# homegreen_node_basic_v1_4_4.net
KiCad netlist of a schematic drawn in EAGLE
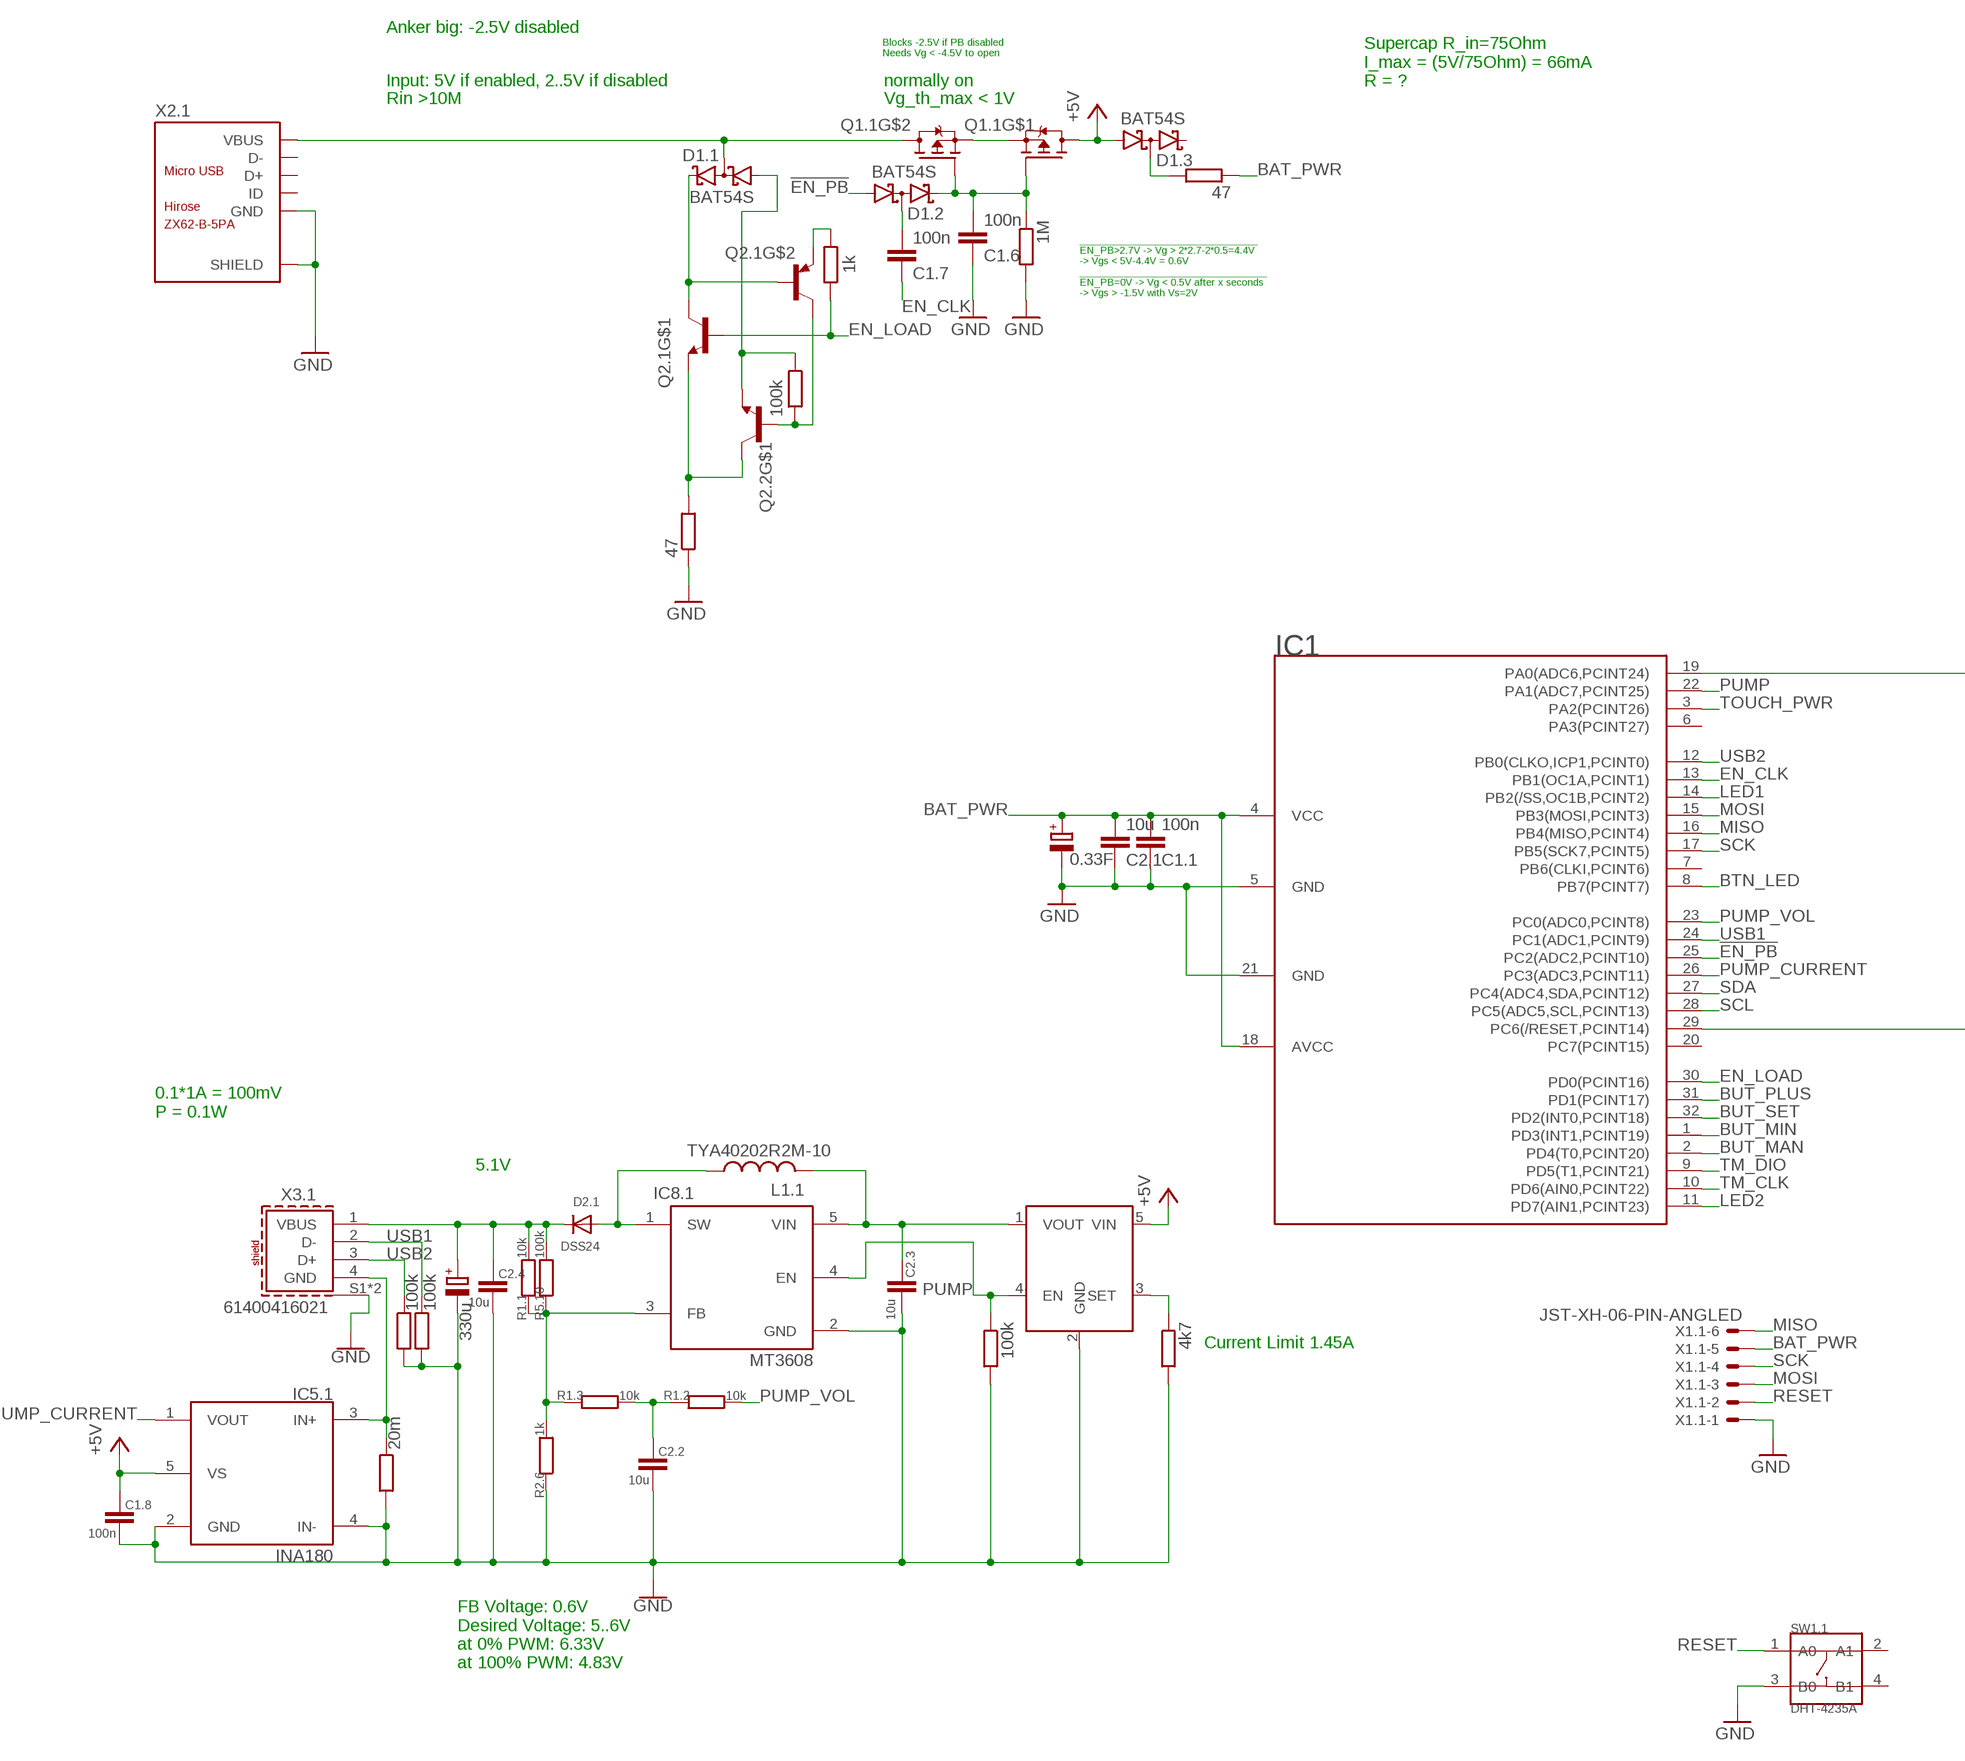
[diagram p0: schematic, sheet 1, part 1 of 2]
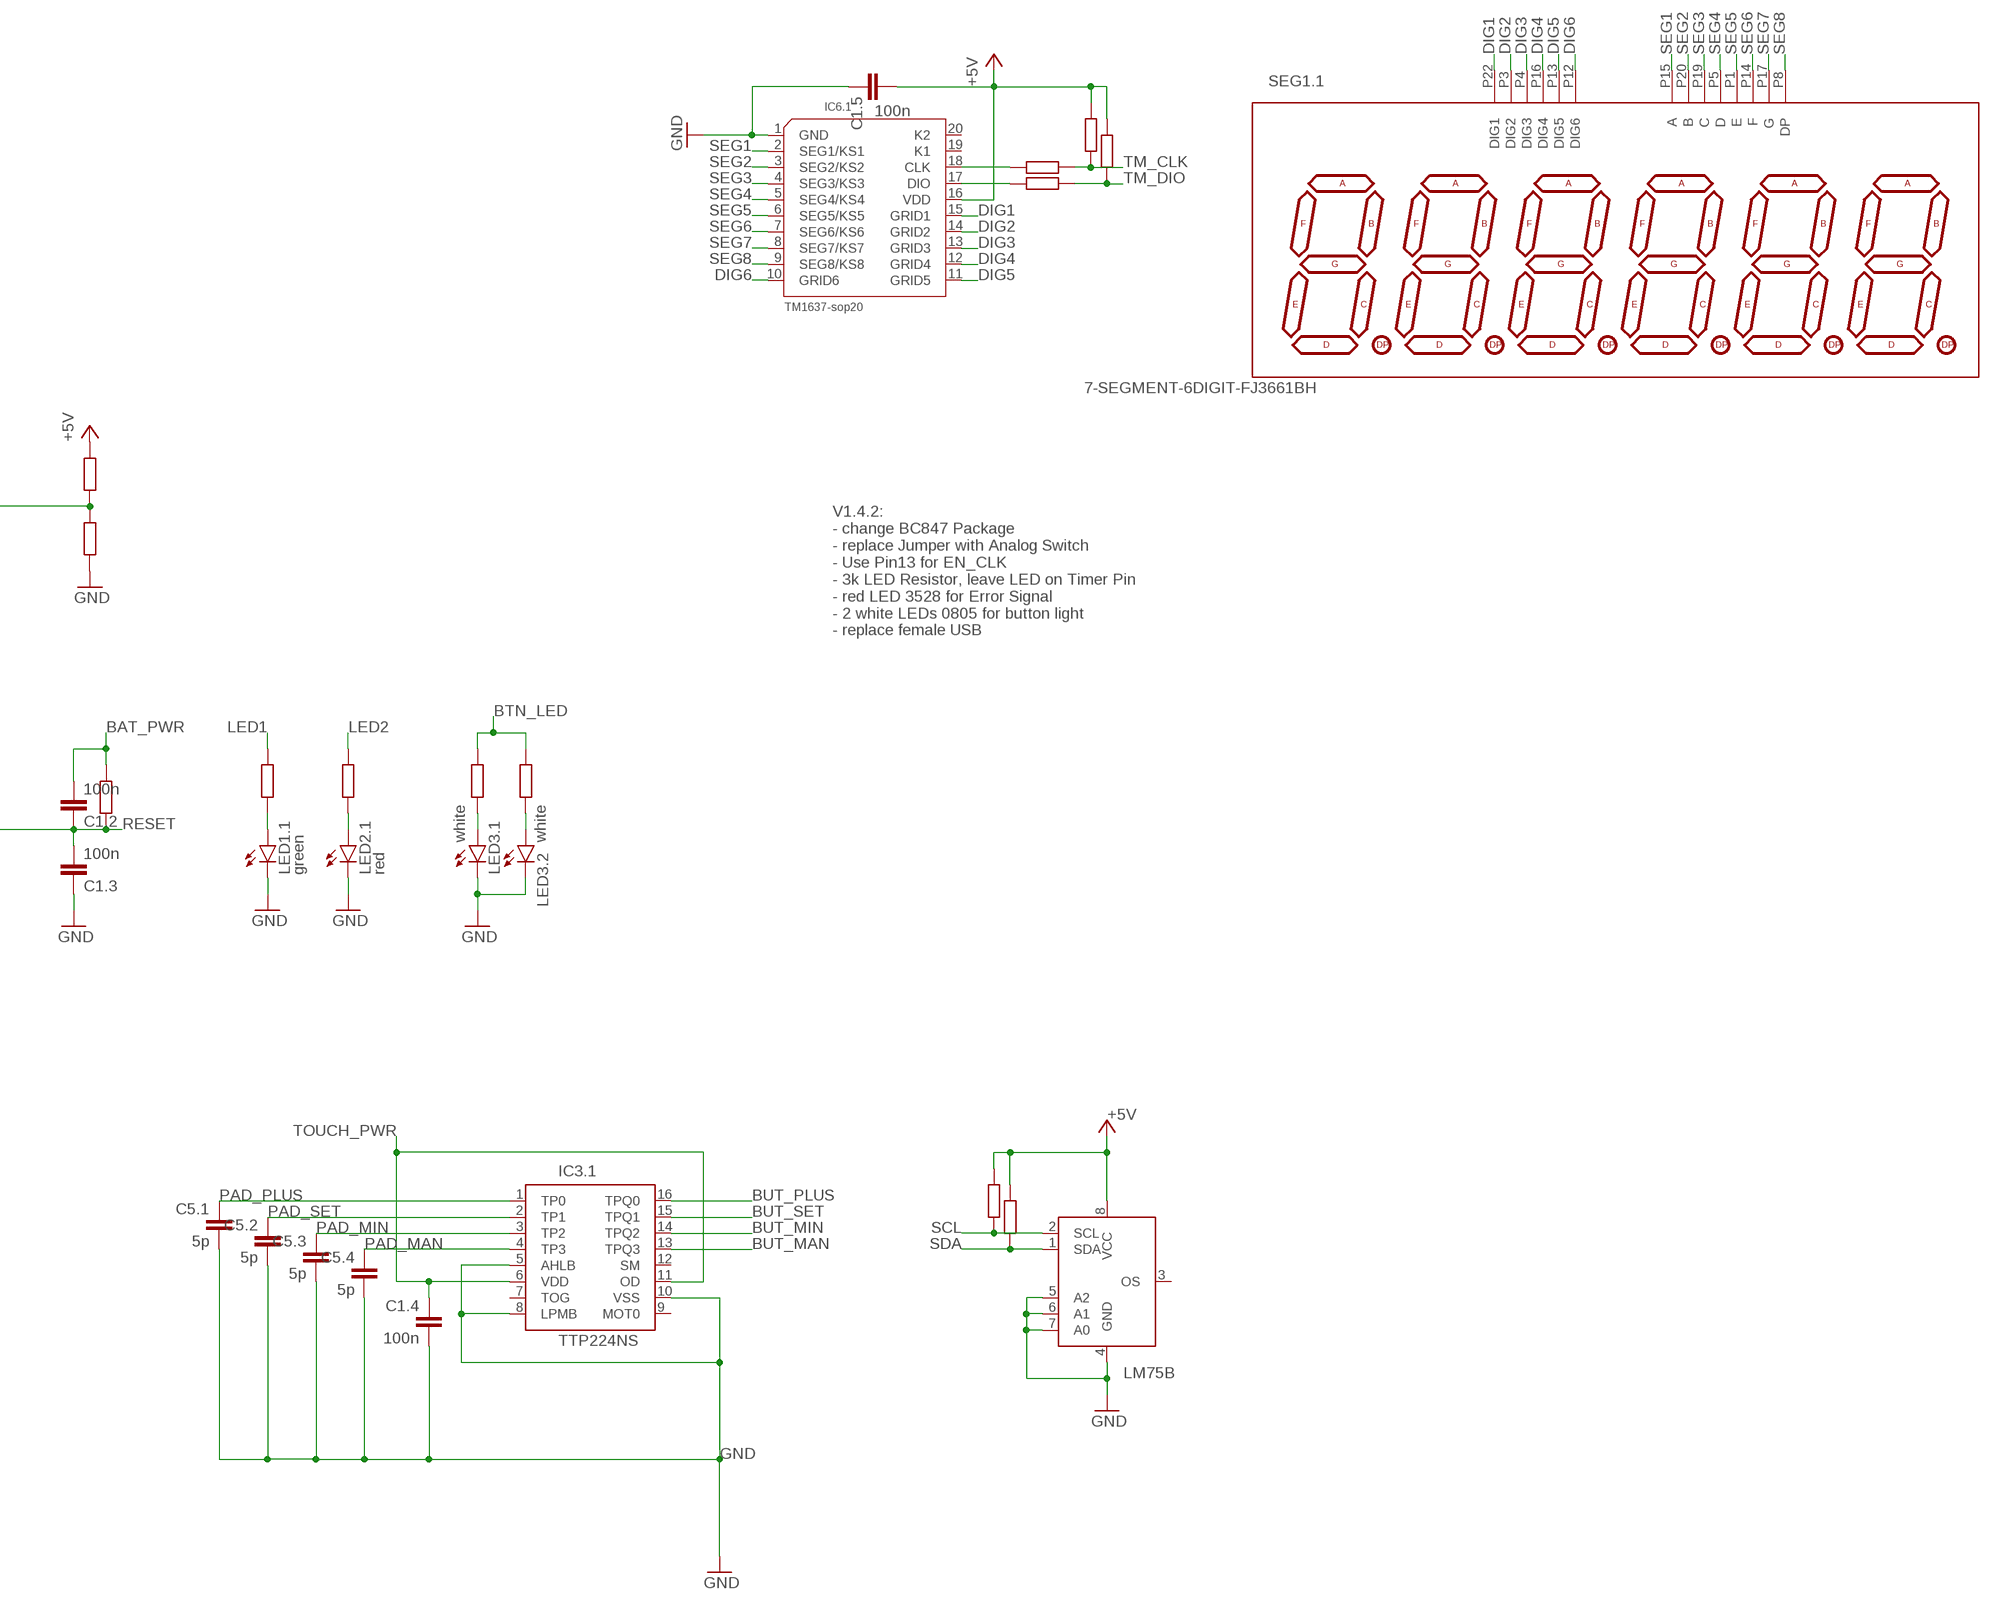
[diagram p1: schematic, sheet 1, part 2 of 2]

(export (version "E")
  (design (tool "Eeschema 10.0.6"))
  (components
    (comp (ref "C1.1")
      (value "100n")
      (footprint "eagle-import:C0805")
      (libsource (lib "eagle-import") (part "C-EUC0805"))
    )
    (comp (ref "C1.2")
      (value "100n")
      (footprint "eagle-import:C0805")
      (libsource (lib "eagle-import") (part "C-EUC0805"))
    )
    (comp (ref "C1.3")
      (value "100n")
      (footprint "eagle-import:C0805")
      (libsource (lib "eagle-import") (part "C-EUC0805"))
    )
    (comp (ref "C1.4")
      (value "100n")
      (footprint "eagle-import:C0805")
      (libsource (lib "eagle-import") (part "C-EUC0805"))
    )
    (comp (ref "C1.5")
      (value "100n")
      (footprint "eagle-import:C0805")
      (libsource (lib "eagle-import") (part "C-EUC0805"))
    )
    (comp (ref "C1.6")
      (value "100n")
      (footprint "eagle-import:C0805")
      (libsource (lib "eagle-import") (part "C-EUC0805"))
    )
    (comp (ref "C1.7")
      (value "100n")
      (footprint "eagle-import:C0805")
      (libsource (lib "eagle-import") (part "C-EUC0805"))
    )
    (comp (ref "C1.8")
      (value "100n")
      (footprint "eagle-import:C0805")
      (libsource (lib "eagle-import") (part "resistor_348_C-EUC0805"))
    )
    (comp (ref "C2.1")
      (value "10u")
      (footprint "eagle-import:C0805")
      (libsource (lib "eagle-import") (part "C-EUC0805"))
    )
    (comp (ref "C2.2")
      (value "10u")
      (footprint "eagle-import:C0805")
      (libsource (lib "eagle-import") (part "resistor_348_C-EUC0805"))
    )
    (comp (ref "C2.3")
      (value "10u")
      (footprint "eagle-import:C0805")
      (libsource (lib "eagle-import") (part "resistor_348_C-EUC0805"))
    )
    (comp (ref "C2.4")
      (value "10u")
      (footprint "eagle-import:C0805")
      (libsource (lib "eagle-import") (part "resistor_348_C-EUC0805"))
    )
    (comp (ref "C3.1")
      (value "0.33F")
      (footprint "eagle-import:C_FYD0H104ZF")
      (libsource (lib "eagle-import") (part "SUPERCAP"))
    )
    (comp (ref "C4.1")
      (value "330u")
      (footprint "eagle-import:PANASONIC_D")
      (libsource (lib "eagle-import") (part "CPOL-EUD"))
    )
    (comp (ref "C5.1")
      (value "5p")
      (footprint "eagle-import:C0805")
      (libsource (lib "eagle-import") (part "C-EUC0805"))
    )
    (comp (ref "C5.2")
      (value "5p")
      (footprint "eagle-import:C0805")
      (libsource (lib "eagle-import") (part "C-EUC0805"))
    )
    (comp (ref "C5.3")
      (value "5p")
      (footprint "eagle-import:C0805")
      (libsource (lib "eagle-import") (part "C-EUC0805"))
    )
    (comp (ref "C5.4")
      (value "5p")
      (footprint "eagle-import:C0805")
      (libsource (lib "eagle-import") (part "C-EUC0805"))
    )
    (comp (ref "D1.1")
      (value "BAT54S")
      (footprint "eagle-import:SOT23")
      (libsource (lib "eagle-import") (part "BAT54S"))
    )
    (comp (ref "D1.2")
      (value "BAT54S")
      (footprint "eagle-import:SOT23")
      (libsource (lib "eagle-import") (part "BAT54S"))
    )
    (comp (ref "D1.3")
      (value "BAT54S")
      (footprint "eagle-import:SOT23")
      (libsource (lib "eagle-import") (part "BAT54S"))
    )
    (comp (ref "D2.1")
      (value "DSS24")
      (footprint "eagle-import:SOD-123")
      (libsource (lib "eagle-import") (part "DIODE_SOD123"))
    )
    (comp (ref "IC1")
      (value "ATTINY88")
      (footprint "eagle-import:TQFP32-08")
      (libsource (lib "eagle-import") (part "ATTINY88"))
    )
    (comp (ref "IC2.1")
      (value "LM75B")
      (footprint "eagle-import:SO8")
      (libsource (lib "eagle-import") (part "LM75B"))
    )
    (comp (ref "IC3.1")
      (value "TTP224NS")
      (footprint "eagle-import:SSOP16")
      (libsource (lib "eagle-import") (part "TTP224NS"))
    )
    (comp (ref "IC4.1")
      (value "MT9700MT9700")
      (footprint "eagle-import:SOT23-5")
      (libsource (lib "eagle-import") (part "MT9700MT9700"))
    )
    (comp (ref "IC5.1")
      (value "INA180")
      (footprint "eagle-import:SOT23-5")
      (libsource (lib "eagle-import") (part "INA180"))
    )
    (comp (ref "IC6.1")
      (value "TM1637-sop20")
      (footprint "eagle-import:SOP20-1.27-12.7X7.65MM")
      (fields (field (name "MPN") "TM1637"))
      (libsource (lib "eagle-import") (part "DRIVER-TM1637(SOP20)"))
    )
    (comp (ref "IC8.1")
      (value "MT3608")
      (footprint "eagle-import:SOT23-6")
      (libsource (lib "eagle-import") (part "MT3608"))
    )
    (comp (ref "L1.1")
      (value "TYA40202R2M-10")
      (footprint "eagle-import:WE-LQSH_4020")
      (libsource (lib "eagle-import") (part "WE-LQSH_4020_744050420047"))
    )
    (comp (ref "LED1.1")
      (value "green")
      (footprint "eagle-import:KA-3528ASYC")
      (libsource (lib "eagle-import") (part "LEDKA-3528ASYC"))
    )
    (comp (ref "LED2.1")
      (value "red")
      (footprint "eagle-import:KA-3528ASYC")
      (libsource (lib "eagle-import") (part "LEDKA-3528ASYC"))
    )
    (comp (ref "LED3.1")
      (value "white")
      (footprint "eagle-import:CHIPLED_0805")
      (libsource (lib "eagle-import") (part "LEDCHIPLED_0805"))
    )
    (comp (ref "LED3.2")
      (value "white")
      (footprint "eagle-import:CHIPLED_0805")
      (libsource (lib "eagle-import") (part "LEDCHIPLED_0805"))
    )
    (comp (ref "Q1.1")
      (value "WST2011")
      (footprint "eagle-import:SOT23-6")
      (libsource (lib "eagle-import") (part "CJL2623SOT23-6"))
    )
    (comp (ref "Q2.1")
      (value "BC817DPN")
      (footprint "eagle-import:SOT23-6")
      (libsource (lib "eagle-import") (part "BC817DPN"))
    )
    (comp (ref "Q2.2")
      (value "BC817DPN")
      (footprint "eagle-import:SOT23-6")
      (libsource (lib "eagle-import") (part "BC817DPN"))
    )
    (comp (ref "R1.1")
      (value "10k")
      (footprint "eagle-import:R0805")
      (libsource (lib "eagle-import") (part "resistor_348_R-EU_R0805"))
    )
    (comp (ref "R1.2")
      (value "10k")
      (footprint "eagle-import:R0805")
      (libsource (lib "eagle-import") (part "resistor_348_R-EU_R0805"))
    )
    (comp (ref "R1.3")
      (value "10k")
      (footprint "eagle-import:R0805")
      (libsource (lib "eagle-import") (part "resistor_348_R-EU_R0805"))
    )
    (comp (ref "R2.1")
      (value "1k")
      (footprint "eagle-import:R0805")
      (libsource (lib "eagle-import") (part "R-EU_R0805"))
    )
    (comp (ref "R2.2")
      (value "1k")
      (footprint "eagle-import:R0805")
      (libsource (lib "eagle-import") (part "R-EU_R0805"))
    )
    (comp (ref "R2.3")
      (value "1k")
      (footprint "eagle-import:R0805")
      (libsource (lib "eagle-import") (part "R-EU_R0805"))
    )
    (comp (ref "R2.4")
      (value "1k")
      (footprint "eagle-import:R0805")
      (libsource (lib "eagle-import") (part "R-EU_R0805"))
    )
    (comp (ref "R2.5")
      (value "1k")
      (footprint "eagle-import:R0805")
      (libsource (lib "eagle-import") (part "R-EU_R0805"))
    )
    (comp (ref "R2.6")
      (value "1k")
      (footprint "eagle-import:R0805")
      (libsource (lib "eagle-import") (part "resistor_348_R-EU_R0805"))
    )
    (comp (ref "R3.1")
      (value "47")
      (footprint "eagle-import:R0805")
      (libsource (lib "eagle-import") (part "R-EU_R0805"))
    )
    (comp (ref "R3.2")
      (value "47")
      (footprint "eagle-import:R0805")
      (libsource (lib "eagle-import") (part "R-EU_R0805"))
    )
    (comp (ref "R4.1")
      (value "3k")
      (footprint "eagle-import:R0805")
      (libsource (lib "eagle-import") (part "R-EU_R0805"))
    )
    (comp (ref "R4.2")
      (value "3k")
      (footprint "eagle-import:R0805")
      (libsource (lib "eagle-import") (part "R-EU_R0805"))
    )
    (comp (ref "R5.1")
      (value "100k")
      (footprint "eagle-import:R0805")
      (libsource (lib "eagle-import") (part "R-EU_R0805"))
    )
    (comp (ref "R5.2")
      (value "100k")
      (footprint "eagle-import:R0805")
      (libsource (lib "eagle-import") (part "R-EU_R0805"))
    )
    (comp (ref "R5.3")
      (value "100k")
      (footprint "eagle-import:R0805")
      (libsource (lib "eagle-import") (part "R-EU_R0805"))
    )
    (comp (ref "R5.4")
      (value "100k")
      (footprint "eagle-import:R0805")
      (libsource (lib "eagle-import") (part "R-EU_R0805"))
    )
    (comp (ref "R5.5")
      (value "100k")
      (footprint "eagle-import:R0805")
      (libsource (lib "eagle-import") (part "R-EU_R0805"))
    )
    (comp (ref "R5.6")
      (value "100k")
      (footprint "eagle-import:R0805")
      (libsource (lib "eagle-import") (part "R-EU_R0805"))
    )
    (comp (ref "R5.7")
      (value "100k")
      (footprint "eagle-import:R0805")
      (libsource (lib "eagle-import") (part "R-EU_R0805"))
    )
    (comp (ref "R5.8")
      (value "100k")
      (footprint "eagle-import:R0805")
      (libsource (lib "eagle-import") (part "R-EU_R0805"))
    )
    (comp (ref "R5.9")
      (value "100k")
      (footprint "eagle-import:R0805")
      (libsource (lib "eagle-import") (part "R-EU_R0805"))
    )
    (comp (ref "R5.10")
      (value "100k")
      (footprint "eagle-import:R0805")
      (libsource (lib "eagle-import") (part "resistor_348_R-EU_R0805"))
    )
    (comp (ref "R6.1")
      (value "1M")
      (footprint "eagle-import:R0805")
      (libsource (lib "eagle-import") (part "R-EU_R0805"))
    )
    (comp (ref "R7.1")
      (value "4k7")
      (footprint "eagle-import:R0805")
      (libsource (lib "eagle-import") (part "R-EU_R0805"))
    )
    (comp (ref "R7.2")
      (value "4k7")
      (footprint "eagle-import:R0805")
      (libsource (lib "eagle-import") (part "R-EU_R0805"))
    )
    (comp (ref "R7.3")
      (value "4k7")
      (footprint "eagle-import:R0805")
      (libsource (lib "eagle-import") (part "R-EU_R0805"))
    )
    (comp (ref "R8.1")
      (value "20m")
      (footprint "eagle-import:R0805")
      (libsource (lib "eagle-import") (part "R-EU_R0805"))
    )
    (comp (ref "SEG1.1")
      (value "7-SEGMENT-6DIGIT-FJ3661BH")
      (footprint "eagle-import:7SEG_6D_FJ3661BH")
      (libsource (lib "eagle-import") (part "7-SEGMENT-6DIGIT-FJ3661BH"))
    )
    (comp (ref "SW1.1")
      (value "DHT-4235A")
      (footprint "eagle-import:SW4-SMD-4.2X3.2X2.5MM")
      (libsource (lib "eagle-import") (part "SMD-BUTTON-TOP-DHT-4235A(4P-4.2X3.2MM)"))
    )
    (comp (ref "X1.1")
      (value "JST-XH-06-PIN-ANGLED")
      (footprint "eagle-import:JST-XH-06-PACKAGE-ROUND-PAD-ANGLED")
      (libsource (lib "eagle-import") (part "JST-XH-06-PIN-ANGLED"))
    )
    (comp (ref "X2.1")
      (value "ZX62-B-5PA")
      (footprint "eagle-import:ZX62-B-5PA")
      (libsource (lib "eagle-import") (part "MICRO-USB-SMD(ZX62-B-5PA)"))
    )
    (comp (ref "X3.1")
      (value "61400416021")
      (footprint "eagle-import:61400416021")
      (libsource (lib "eagle-import") (part "61400416021"))
    )
  )
  (nets
    (net (code "1") (name "+5V") (class "Default")
      (node (ref "C1.5") (pin "2") (pinfunction "2_2") (pintype "passive"))
      (node (ref "C1.8") (pin "1") (pinfunction "1_1") (pintype "passive"))
      (node (ref "D1.3") (pin "1") (pinfunction "A1_1") (pintype "passive"))
      (node (ref "IC2.1") (pin "8") (pinfunction "VCC_8") (pintype "power_in"))
      (node (ref "IC4.1") (pin "5") (pinfunction "VIN_5") (pintype "bidirectional"))
      (node (ref "IC5.1") (pin "5") (pinfunction "VS_5") (pintype "bidirectional"))
      (node (ref "IC6.1") (pin "16") (pinfunction "VDD_16") (pintype "bidirectional"))
      (node (ref "Q1.1") (pin "6") (pinfunction "D_6") (pintype "passive"))
      (node (ref "R5.3") (pin "1") (pinfunction "1_1") (pintype "passive"))
      (node (ref "R5.5") (pin "2") (pinfunction "2_2") (pintype "passive"))
      (node (ref "R5.6") (pin "2") (pinfunction "2_2") (pintype "passive"))
      (node (ref "R7.2") (pin "2") (pinfunction "2_2") (pintype "passive"))
      (node (ref "R7.3") (pin "2") (pinfunction "2_2") (pintype "passive"))
    )
    (net (code "2") (name "/BAT_PWR") (class "Default")
      (node (ref "C1.1") (pin "2") (pinfunction "2_2") (pintype "passive"))
      (node (ref "C1.2") (pin "2") (pinfunction "2_2") (pintype "passive"))
      (node (ref "C2.1") (pin "2") (pinfunction "2_2") (pintype "passive"))
      (node (ref "C3.1") (pin "+") (pinfunction "+_+") (pintype "passive"))
      (node (ref "IC1") (pin "18") (pinfunction "AVCC_18") (pintype "power_in"))
      (node (ref "IC1") (pin "4") (pinfunction "VCC_4") (pintype "power_in"))
      (node (ref "R3.2") (pin "1") (pinfunction "1_1") (pintype "passive"))
      (node (ref "R5.7") (pin "1") (pinfunction "1_1") (pintype "passive"))
      (node (ref "X1.1") (pin "5") (pinfunction "S_5") (pintype "passive"))
    )
    (net (code "3") (name "/BTN_LED") (class "Default")
      (node (ref "IC1") (pin "8") (pinfunction "PB7(PCINT7)_8") (pintype "bidirectional"))
      (node (ref "R2.1") (pin "2") (pinfunction "2_2") (pintype "passive"))
      (node (ref "R2.5") (pin "2") (pinfunction "2_2") (pintype "passive"))
    )
    (net (code "4") (name "/BUT_MAN") (class "Default")
      (node (ref "IC1") (pin "2") (pinfunction "PD4(T0,PCINT20)_2") (pintype "bidirectional"))
      (node (ref "IC3.1") (pin "13") (pinfunction "TPQ3_13") (pintype "bidirectional"))
    )
    (net (code "5") (name "/BUT_MIN") (class "Default")
      (node (ref "IC1") (pin "1") (pinfunction "PD3(INT1,PCINT19)_1") (pintype "bidirectional"))
      (node (ref "IC3.1") (pin "14") (pinfunction "TPQ2_14") (pintype "bidirectional"))
    )
    (net (code "6") (name "/BUT_PLUS") (class "Default")
      (node (ref "IC1") (pin "31") (pinfunction "PD1(PCINT17)_31") (pintype "bidirectional"))
      (node (ref "IC3.1") (pin "16") (pinfunction "TPQ0_16") (pintype "bidirectional"))
    )
    (net (code "7") (name "/BUT_SET") (class "Default")
      (node (ref "IC1") (pin "32") (pinfunction "PD2(INT0,PCINT18)_32") (pintype "bidirectional"))
      (node (ref "IC3.1") (pin "15") (pinfunction "TPQ1_15") (pintype "bidirectional"))
    )
    (net (code "8") (name "/DIG1") (class "Default")
      (node (ref "IC6.1") (pin "15") (pinfunction "GRID1_15") (pintype "bidirectional"))
      (node (ref "SEG1.1") (pin "P22") (pinfunction "DIG1_P22") (pintype "bidirectional"))
    )
    (net (code "9") (name "/DIG2") (class "Default")
      (node (ref "IC6.1") (pin "14") (pinfunction "GRID2_14") (pintype "bidirectional"))
      (node (ref "SEG1.1") (pin "P3") (pinfunction "DIG2_P3") (pintype "bidirectional"))
    )
    (net (code "10") (name "/DIG3") (class "Default")
      (node (ref "IC6.1") (pin "13") (pinfunction "GRID3_13") (pintype "bidirectional"))
      (node (ref "SEG1.1") (pin "P4") (pinfunction "DIG3_P4") (pintype "bidirectional"))
    )
    (net (code "11") (name "/DIG4") (class "Default")
      (node (ref "IC6.1") (pin "12") (pinfunction "GRID4_12") (pintype "bidirectional"))
      (node (ref "SEG1.1") (pin "P16") (pinfunction "DIG4_P16") (pintype "bidirectional"))
    )
    (net (code "12") (name "/DIG5") (class "Default")
      (node (ref "IC6.1") (pin "11") (pinfunction "GRID5_11") (pintype "bidirectional"))
      (node (ref "SEG1.1") (pin "P13") (pinfunction "DIG5_P13") (pintype "bidirectional"))
    )
    (net (code "13") (name "/DIG6") (class "Default")
      (node (ref "IC6.1") (pin "10") (pinfunction "GRID6_10") (pintype "bidirectional"))
      (node (ref "SEG1.1") (pin "P12") (pinfunction "DIG6_P12") (pintype "bidirectional"))
    )
    (net (code "14") (name "/EN_CLK") (class "Default")
      (node (ref "C1.7") (pin "1") (pinfunction "1_1") (pintype "passive"))
      (node (ref "IC1") (pin "13") (pinfunction "PB1(OC1A,PCINT1)_13") (pintype "bidirectional"))
    )
    (net (code "15") (name "/EN_LOAD") (class "Default")
      (node (ref "IC1") (pin "30") (pinfunction "PD0(PCINT16)_30") (pintype "bidirectional"))
      (node (ref "Q2.1") (pin "2") (pinfunction "B_2") (pintype "passive"))
      (node (ref "R2.4") (pin "1") (pinfunction "1_1") (pintype "passive"))
    )
    (net (code "16") (name "/LED1") (class "Default")
      (node (ref "IC1") (pin "14") (pinfunction "PB2(/SS,OC1B,PCINT2)_14") (pintype "bidirectional"))
      (node (ref "R4.1") (pin "2") (pinfunction "2_2") (pintype "passive"))
    )
    (net (code "17") (name "/LED2") (class "Default")
      (node (ref "IC1") (pin "11") (pinfunction "PD7(AIN1,PCINT23)_11") (pintype "bidirectional"))
      (node (ref "R4.2") (pin "2") (pinfunction "2_2") (pintype "passive"))
    )
    (net (code "18") (name "/MISO") (class "Default")
      (node (ref "IC1") (pin "16") (pinfunction "PB4(MISO,PCINT4)_16") (pintype "bidirectional"))
      (node (ref "X1.1") (pin "6") (pinfunction "S_6") (pintype "passive"))
    )
    (net (code "19") (name "/MOSI") (class "Default")
      (node (ref "IC1") (pin "15") (pinfunction "PB3(MOSI,PCINT3)_15") (pintype "bidirectional"))
      (node (ref "X1.1") (pin "3") (pinfunction "S_3") (pintype "passive"))
    )
    (net (code "20") (name "/PAD_MAN") (class "Default")
      (node (ref "C5.4") (pin "1") (pinfunction "1_1") (pintype "passive"))
      (node (ref "IC3.1") (pin "4") (pinfunction "TP3_4") (pintype "bidirectional"))
    )
    (net (code "21") (name "/PAD_MIN") (class "Default")
      (node (ref "C5.3") (pin "1") (pinfunction "1_1") (pintype "passive"))
      (node (ref "IC3.1") (pin "3") (pinfunction "TP2_3") (pintype "bidirectional"))
    )
    (net (code "22") (name "/PAD_PLUS") (class "Default")
      (node (ref "C5.1") (pin "1") (pinfunction "1_1") (pintype "passive"))
      (node (ref "IC3.1") (pin "1") (pinfunction "TP0_1") (pintype "bidirectional"))
    )
    (net (code "23") (name "/PAD_SET") (class "Default")
      (node (ref "C5.2") (pin "1") (pinfunction "1_1") (pintype "passive"))
      (node (ref "IC3.1") (pin "2") (pinfunction "TP1_2") (pintype "bidirectional"))
    )
    (net (code "24") (name "/PUMP") (class "Default")
      (node (ref "IC1") (pin "22") (pinfunction "PA1(ADC7,PCINT25)_22") (pintype "bidirectional"))
      (node (ref "IC4.1") (pin "4") (pinfunction "EN_4") (pintype "bidirectional"))
      (node (ref "IC8.1") (pin "4") (pinfunction "EN_4") (pintype "bidirectional"))
      (node (ref "R5.2") (pin "1") (pinfunction "1_1") (pintype "passive"))
    )
    (net (code "25") (name "/PUMP_CURRENT") (class "Default")
      (node (ref "IC1") (pin "26") (pinfunction "PC3(ADC3,PCINT11)_26") (pintype "bidirectional"))
      (node (ref "IC5.1") (pin "1") (pinfunction "VOUT_1") (pintype "bidirectional"))
    )
    (net (code "26") (name "/PUMP_VOL") (class "Default")
      (node (ref "IC1") (pin "23") (pinfunction "PC0(ADC0,PCINT8)_23") (pintype "bidirectional"))
      (node (ref "R1.2") (pin "2") (pinfunction "2_2") (pintype "passive"))
    )
    (net (code "27") (name "/RESET") (class "Default")
      (node (ref "C1.2") (pin "1") (pinfunction "1_1") (pintype "passive"))
      (node (ref "C1.3") (pin "2") (pinfunction "2_2") (pintype "passive"))
      (node (ref "IC1") (pin "29") (pinfunction "PC6(/RESET,PCINT14)_29") (pintype "bidirectional"))
      (node (ref "R5.7") (pin "2") (pinfunction "2_2") (pintype "passive"))
      (node (ref "SW1.1") (pin "1") (pinfunction "A0_1") (pintype "bidirectional"))
      (node (ref "X1.1") (pin "2") (pinfunction "S_2") (pintype "passive"))
    )
    (net (code "28") (name "/SCK") (class "Default")
      (node (ref "IC1") (pin "17") (pinfunction "PB5(SCK7,PCINT5)_17") (pintype "bidirectional"))
      (node (ref "X1.1") (pin "4") (pinfunction "S_4") (pintype "passive"))
    )
    (net (code "29") (name "/SCL") (class "Default")
      (node (ref "IC1") (pin "28") (pinfunction "PC5(ADC5,SCL,PCINT13)_28") (pintype "bidirectional"))
      (node (ref "IC2.1") (pin "2") (pinfunction "SCL_2") (pintype "bidirectional"))
      (node (ref "R7.3") (pin "1") (pinfunction "1_1") (pintype "passive"))
    )
    (net (code "30") (name "/SDA") (class "Default")
      (node (ref "IC1") (pin "27") (pinfunction "PC4(ADC4,SDA,PCINT12)_27") (pintype "bidirectional"))
      (node (ref "IC2.1") (pin "1") (pinfunction "SDA_1") (pintype "bidirectional"))
      (node (ref "R7.2") (pin "1") (pinfunction "1_1") (pintype "passive"))
    )
    (net (code "31") (name "/SEG1") (class "Default")
      (node (ref "IC6.1") (pin "2") (pinfunction "SEG1/KS1_2") (pintype "bidirectional"))
      (node (ref "SEG1.1") (pin "P15") (pinfunction "A_P15") (pintype "bidirectional"))
    )
    (net (code "32") (name "/SEG2") (class "Default")
      (node (ref "IC6.1") (pin "3") (pinfunction "SEG2/KS2_3") (pintype "bidirectional"))
      (node (ref "SEG1.1") (pin "P20") (pinfunction "B_P20") (pintype "bidirectional"))
    )
    (net (code "33") (name "/SEG3") (class "Default")
      (node (ref "IC6.1") (pin "4") (pinfunction "SEG3/KS3_4") (pintype "bidirectional"))
      (node (ref "SEG1.1") (pin "P19") (pinfunction "C_P19") (pintype "bidirectional"))
    )
    (net (code "34") (name "/SEG4") (class "Default")
      (node (ref "IC6.1") (pin "5") (pinfunction "SEG4/KS4_5") (pintype "bidirectional"))
      (node (ref "SEG1.1") (pin "P5") (pinfunction "D_P5") (pintype "bidirectional"))
    )
    (net (code "35") (name "/SEG5") (class "Default")
      (node (ref "IC6.1") (pin "6") (pinfunction "SEG5/KS5_6") (pintype "bidirectional"))
      (node (ref "SEG1.1") (pin "P1") (pinfunction "E_P1") (pintype "bidirectional"))
    )
    (net (code "36") (name "/SEG6") (class "Default")
      (node (ref "IC6.1") (pin "7") (pinfunction "SEG6/KS6_7") (pintype "bidirectional"))
      (node (ref "SEG1.1") (pin "P14") (pinfunction "F_P14") (pintype "bidirectional"))
    )
    (net (code "37") (name "/SEG7") (class "Default")
      (node (ref "IC6.1") (pin "8") (pinfunction "SEG7/KS7_8") (pintype "bidirectional"))
      (node (ref "SEG1.1") (pin "P17") (pinfunction "G_P17") (pintype "bidirectional"))
    )
    (net (code "38") (name "/SEG8") (class "Default")
      (node (ref "IC6.1") (pin "9") (pinfunction "SEG8/KS8_9") (pintype "bidirectional"))
      (node (ref "SEG1.1") (pin "P8") (pinfunction "DP_P8") (pintype "bidirectional"))
    )
    (net (code "39") (name "/TM_CLK") (class "Default")
      (node (ref "IC1") (pin "10") (pinfunction "PD6(AIN0,PCINT22)_10") (pintype "bidirectional"))
      (node (ref "R2.2") (pin "1") (pinfunction "1_1") (pintype "passive"))
      (node (ref "R5.5") (pin "1") (pinfunction "1_1") (pintype "passive"))
    )
    (net (code "40") (name "/TM_DIO") (class "Default")
      (node (ref "IC1") (pin "9") (pinfunction "PD5(T1,PCINT21)_9") (pintype "bidirectional"))
      (node (ref "R2.3") (pin "1") (pinfunction "1_1") (pintype "passive"))
      (node (ref "R5.6") (pin "1") (pinfunction "1_1") (pintype "passive"))
    )
    (net (code "41") (name "/TOUCH_PWR") (class "Default")
      (node (ref "C1.4") (pin "1") (pinfunction "1_1") (pintype "passive"))
      (node (ref "IC1") (pin "3") (pinfunction "PA2(PCINT26)_3") (pintype "bidirectional"))
      (node (ref "IC3.1") (pin "11") (pinfunction "OD_11") (pintype "bidirectional"))
      (node (ref "IC3.1") (pin "6") (pinfunction "VDD_6") (pintype "power_in"))
    )
    (net (code "42") (name "/USB1") (class "Default")
      (node (ref "IC1") (pin "24") (pinfunction "PC1(ADC1,PCINT9)_24") (pintype "bidirectional"))
      (node (ref "R5.9") (pin "1") (pinfunction "1_1") (pintype "passive"))
      (node (ref "X3.1") (pin "2") (pinfunction "D-_2") (pintype "bidirectional"))
    )
    (net (code "43") (name "/USB2") (class "Default")
      (node (ref "IC1") (pin "12") (pinfunction "PB0(CLKO,ICP1,PCINT0)_12") (pintype "bidirectional"))
      (node (ref "R5.8") (pin "1") (pinfunction "1_1") (pintype "passive"))
      (node (ref "X3.1") (pin "3") (pinfunction "D+_3") (pintype "bidirectional"))
    )
    (net (code "44") (name "/~{EN_PB}") (class "Default")
      (node (ref "D1.2") (pin "1") (pinfunction "A1_1") (pintype "passive"))
      (node (ref "IC1") (pin "25") (pinfunction "PC2(ADC2,PCINT10)_25") (pintype "bidirectional"))
    )
    (net (code "45") (name "GND") (class "Default")
      (node (ref "C1.1") (pin "1") (pinfunction "1_1") (pintype "passive"))
      (node (ref "C1.3") (pin "1") (pinfunction "1_1") (pintype "passive"))
      (node (ref "C1.4") (pin "2") (pinfunction "2_2") (pintype "passive"))
      (node (ref "C1.5") (pin "1") (pinfunction "1_1") (pintype "passive"))
      (node (ref "C1.6") (pin "1") (pinfunction "1_1") (pintype "passive"))
      (node (ref "C1.8") (pin "2") (pinfunction "2_2") (pintype "passive"))
      (node (ref "C2.1") (pin "1") (pinfunction "1_1") (pintype "passive"))
      (node (ref "C2.2") (pin "2") (pinfunction "2_2") (pintype "passive"))
      (node (ref "C2.3") (pin "2") (pinfunction "2_2") (pintype "passive"))
      (node (ref "C2.4") (pin "2") (pinfunction "2_2") (pintype "passive"))
      (node (ref "C3.1") (pin "-") (pinfunction "-_-") (pintype "passive"))
      (node (ref "C4.1") (pin "-") (pinfunction "-_-") (pintype "passive"))
      (node (ref "C5.1") (pin "2") (pinfunction "2_2") (pintype "passive"))
      (node (ref "C5.2") (pin "2") (pinfunction "2_2") (pintype "passive"))
      (node (ref "C5.3") (pin "2") (pinfunction "2_2") (pintype "passive"))
      (node (ref "C5.4") (pin "2") (pinfunction "2_2") (pintype "passive"))
      (node (ref "IC1") (pin "21") (pinfunction "GND_21") (pintype "power_in"))
      (node (ref "IC1") (pin "5") (pinfunction "GND_5") (pintype "power_in"))
      (node (ref "IC2.1") (pin "4") (pinfunction "GND_4") (pintype "bidirectional"))
      (node (ref "IC2.1") (pin "5") (pinfunction "A2_5") (pintype "input"))
      (node (ref "IC2.1") (pin "6") (pinfunction "A1_6") (pintype "input"))
      (node (ref "IC2.1") (pin "7") (pinfunction "A0_7") (pintype "input"))
      (node (ref "IC3.1") (pin "10") (pinfunction "VSS_10") (pintype "power_in"))
      (node (ref "IC3.1") (pin "5") (pinfunction "AHLB_5") (pintype "bidirectional"))
      (node (ref "IC3.1") (pin "8") (pinfunction "LPMB_8") (pintype "bidirectional"))
      (node (ref "IC4.1") (pin "2") (pinfunction "GND_2") (pintype "bidirectional"))
      (node (ref "IC5.1") (pin "2") (pinfunction "GND_2") (pintype "bidirectional"))
      (node (ref "IC5.1") (pin "4") (pinfunction "IN-_4") (pintype "bidirectional"))
      (node (ref "IC6.1") (pin "1") (pinfunction "GND_1") (pintype "bidirectional"))
      (node (ref "IC8.1") (pin "2") (pinfunction "GND_2") (pintype "bidirectional"))
      (node (ref "LED1.1") (pin "C") (pinfunction "C_C") (pintype "passive"))
      (node (ref "LED2.1") (pin "C") (pinfunction "C_C") (pintype "passive"))
      (node (ref "LED3.1") (pin "C") (pinfunction "C_C") (pintype "passive"))
      (node (ref "LED3.2") (pin "C") (pinfunction "C_C") (pintype "passive"))
      (node (ref "R2.6") (pin "1") (pinfunction "1_1") (pintype "passive"))
      (node (ref "R3.1") (pin "1") (pinfunction "1_1") (pintype "passive"))
      (node (ref "R5.2") (pin "2") (pinfunction "2_2") (pintype "passive"))
      (node (ref "R5.4") (pin "2") (pinfunction "2_2") (pintype "passive"))
      (node (ref "R5.8") (pin "2") (pinfunction "2_2") (pintype "passive"))
      (node (ref "R5.9") (pin "2") (pinfunction "2_2") (pintype "passive"))
      (node (ref "R6.1") (pin "2") (pinfunction "2_2") (pintype "passive"))
      (node (ref "R7.1") (pin "2") (pinfunction "2_2") (pintype "passive"))
      (node (ref "R8.1") (pin "2") (pinfunction "2_2") (pintype "passive"))
      (node (ref "SW1.1") (pin "3") (pinfunction "B0_3") (pintype "bidirectional"))
      (node (ref "X1.1") (pin "1") (pinfunction "S_1") (pintype "passive"))
      (node (ref "X2.1") (pin "5") (pinfunction "GND_5") (pintype "power_in"))
      (node (ref "X2.1") (pin "P1") (pinfunction "SHIELD_P1") (pintype "power_in"))
      (node (ref "X2.1") (pin "P2") (pinfunction "SHIELD_P2") (pintype "power_in"))
      (node (ref "X2.1") (pin "P3") (pinfunction "SHIELD_P3") (pintype "power_in"))
      (node (ref "X2.1") (pin "P4") (pinfunction "SHIELD_P4") (pintype "power_in"))
      (node (ref "X2.1") (pin "P5") (pinfunction "SHIELD_P5") (pintype "power_in"))
      (node (ref "X2.1") (pin "P6") (pinfunction "SHIELD_P6") (pintype "power_in"))
      (node (ref "X3.1") (pin "S1") (pinfunction "SHIELD_S1") (pintype "bidirectional"))
      (node (ref "X3.1") (pin "S2") (pinfunction "SHIELD_S2") (pintype "bidirectional"))
    )
    (net (code "46") (name "Net-(C2.2-Pad1)") (class "Default")
      (node (ref "C2.2") (pin "1") (pinfunction "1_1") (pintype "passive"))
      (node (ref "R1.2") (pin "1") (pinfunction "1_1") (pintype "passive"))
      (node (ref "R1.3") (pin "2") (pinfunction "2_2") (pintype "passive"))
    )
    (net (code "47") (name "Net-(D1.1-A1)") (class "Default")
      (node (ref "D1.1") (pin "1") (pinfunction "A1_1") (pintype "passive"))
      (node (ref "Q2.2") (pin "1") (pinfunction "E_1") (pintype "passive"))
      (node (ref "R5.1") (pin "1") (pinfunction "1_1") (pintype "passive"))
    )
    (net (code "48") (name "Net-(D1.1-C1A2)") (class "Default")
      (node (ref "D1.1") (pin "3") (pinfunction "C1A2_3") (pintype "passive"))
      (node (ref "Q1.1") (pin "4") (pinfunction "D_4") (pintype "passive"))
      (node (ref "X2.1") (pin "1") (pinfunction "VBUS_1") (pintype "power_in"))
    )
    (net (code "49") (name "Net-(D1.1-C2)") (class "Default")
      (node (ref "D1.1") (pin "2") (pinfunction "C2_2") (pintype "passive"))
      (node (ref "Q2.1") (pin "5") (pinfunction "B_5") (pintype "passive"))
      (node (ref "Q2.1") (pin "6") (pinfunction "C_6") (pintype "passive"))
    )
    (net (code "50") (name "Net-(D1.2-C1A2)") (class "Default")
      (node (ref "C1.7") (pin "2") (pinfunction "2_2") (pintype "passive"))
      (node (ref "D1.2") (pin "3") (pinfunction "C1A2_3") (pintype "passive"))
    )
    (net (code "51") (name "Net-(D1.2-C2)") (class "Default")
      (node (ref "C1.6") (pin "2") (pinfunction "2_2") (pintype "passive"))
      (node (ref "D1.2") (pin "2") (pinfunction "C2_2") (pintype "passive"))
      (node (ref "Q1.1") (pin "1") (pinfunction "G_1") (pintype "passive"))
      (node (ref "Q1.1") (pin "3") (pinfunction "G_3") (pintype "passive"))
      (node (ref "R6.1") (pin "1") (pinfunction "1_1") (pintype "passive"))
    )
    (net (code "52") (name "Net-(D1.3-C1A2)") (class "Default")
      (node (ref "D1.3") (pin "3") (pinfunction "C1A2_3") (pintype "passive"))
      (node (ref "R3.2") (pin "2") (pinfunction "2_2") (pintype "passive"))
    )
    (net (code "53") (name "Net-(IC1-PA0(ADC6,PCINT24))") (class "Default")
      (node (ref "IC1") (pin "19") (pinfunction "PA0(ADC6,PCINT24)_19") (pintype "bidirectional"))
      (node (ref "R5.3") (pin "2") (pinfunction "2_2") (pintype "passive"))
      (node (ref "R5.4") (pin "1") (pinfunction "1_1") (pintype "passive"))
    )
    (net (code "54") (name "Net-(IC4.1-SET)") (class "Default")
      (node (ref "IC4.1") (pin "3") (pinfunction "SET_3") (pintype "bidirectional"))
      (node (ref "R7.1") (pin "1") (pinfunction "1_1") (pintype "passive"))
    )
    (net (code "55") (name "Net-(IC4.1-VOUT)") (class "Default")
      (node (ref "C2.3") (pin "1") (pinfunction "1_1") (pintype "passive"))
      (node (ref "IC4.1") (pin "1") (pinfunction "VOUT_1") (pintype "bidirectional"))
      (node (ref "IC8.1") (pin "5") (pinfunction "VIN_5") (pintype "bidirectional"))
      (node (ref "L1.1") (pin "1") (pinfunction "1_1") (pintype "passive"))
    )
    (net (code "56") (name "Net-(IC5.1-IN+)") (class "Default")
      (node (ref "IC5.1") (pin "3") (pinfunction "IN+_3") (pintype "bidirectional"))
      (node (ref "R8.1") (pin "1") (pinfunction "1_1") (pintype "passive"))
      (node (ref "X3.1") (pin "4") (pinfunction "GND_4") (pintype "bidirectional"))
    )
    (net (code "57") (name "Net-(IC6.1-CLK)") (class "Default")
      (node (ref "IC6.1") (pin "18") (pinfunction "CLK_18") (pintype "bidirectional"))
      (node (ref "R2.2") (pin "2") (pinfunction "2_2") (pintype "passive"))
    )
    (net (code "58") (name "Net-(IC6.1-DIO)") (class "Default")
      (node (ref "IC6.1") (pin "17") (pinfunction "DIO_17") (pintype "bidirectional"))
      (node (ref "R2.3") (pin "2") (pinfunction "2_2") (pintype "passive"))
    )
    (net (code "59") (name "Net-(IC8.1-FB)") (class "Default")
      (node (ref "IC8.1") (pin "3") (pinfunction "FB_3") (pintype "bidirectional"))
      (node (ref "R1.1") (pin "1") (pinfunction "1_1") (pintype "passive"))
      (node (ref "R1.3") (pin "1") (pinfunction "1_1") (pintype "passive"))
      (node (ref "R2.6") (pin "2") (pinfunction "2_2") (pintype "passive"))
      (node (ref "R5.10") (pin "1") (pinfunction "1_1") (pintype "passive"))
    )
    (net (code "60") (name "Net-(IC8.1-SW)") (class "Default")
      (node (ref "D2.1") (pin "A") (pinfunction "A_A") (pintype "passive"))
      (node (ref "IC8.1") (pin "1") (pinfunction "SW_1") (pintype "bidirectional"))
      (node (ref "L1.1") (pin "2") (pinfunction "2_2") (pintype "passive"))
    )
    (net (code "61") (name "Net-(LED1.1-PadA)") (class "Default")
      (node (ref "LED1.1") (pin "A") (pinfunction "A_A") (pintype "passive"))
      (node (ref "R4.1") (pin "1") (pinfunction "1_1") (pintype "passive"))
    )
    (net (code "62") (name "Net-(LED2.1-PadA)") (class "Default")
      (node (ref "LED2.1") (pin "A") (pinfunction "A_A") (pintype "passive"))
      (node (ref "R4.2") (pin "1") (pinfunction "1_1") (pintype "passive"))
    )
    (net (code "63") (name "Net-(LED3.1-PadA)") (class "Default")
      (node (ref "LED3.1") (pin "A") (pinfunction "A_A") (pintype "passive"))
      (node (ref "R2.1") (pin "1") (pinfunction "1_1") (pintype "passive"))
    )
    (net (code "64") (name "Net-(LED3.2-PadA)") (class "Default")
      (node (ref "LED3.2") (pin "A") (pinfunction "A_A") (pintype "passive"))
      (node (ref "R2.5") (pin "1") (pinfunction "1_1") (pintype "passive"))
    )
    (net (code "65") (name "Net-(Q1.1A-S)") (class "Default")
      (node (ref "Q1.1") (pin "2") (pinfunction "S_2") (pintype "passive"))
      (node (ref "Q1.1") (pin "5") (pinfunction "S_5") (pintype "passive"))
    )
    (net (code "66") (name "Net-(Q2.1A-E)") (class "Default")
      (node (ref "Q2.1") (pin "1") (pinfunction "E_1") (pintype "passive"))
      (node (ref "Q2.2") (pin "6") (pinfunction "C_6") (pintype "passive"))
      (node (ref "R3.1") (pin "2") (pinfunction "2_2") (pintype "passive"))
    )
    (net (code "67") (name "Net-(Q2.1B-C)") (class "Default")
      (node (ref "Q2.1") (pin "3") (pinfunction "C_3") (pintype "passive"))
      (node (ref "Q2.2") (pin "2") (pinfunction "B_2") (pintype "passive"))
      (node (ref "R5.1") (pin "2") (pinfunction "2_2") (pintype "passive"))
    )
    (net (code "68") (name "Net-(Q2.1B-E)") (class "Default")
      (node (ref "Q2.1") (pin "4") (pinfunction "E_4") (pintype "passive"))
      (node (ref "R2.4") (pin "2") (pinfunction "2_2") (pintype "passive"))
    )
    (net (code "69") (name "Net-(X3.1-VBUS)") (class "Default")
      (node (ref "C2.4") (pin "1") (pinfunction "1_1") (pintype "passive"))
      (node (ref "C4.1") (pin "+") (pinfunction "+_+") (pintype "passive"))
      (node (ref "D2.1") (pin "C") (pinfunction "C_C") (pintype "passive"))
      (node (ref "R1.1") (pin "2") (pinfunction "2_2") (pintype "passive"))
      (node (ref "R5.10") (pin "2") (pinfunction "2_2") (pintype "passive"))
      (node (ref "X3.1") (pin "1") (pinfunction "VBUS_1") (pintype "bidirectional"))
    )
    (net (code "70") (name "unconnected-(D1.3-C2-Pad2)") (class "Default")
      (node (ref "D1.3") (pin "2") (pinfunction "C2_2") (pintype "passive"))
    )
    (net (code "71") (name "unconnected-(IC1-PA3(PCINT27)-Pad6)") (class "Default")
      (node (ref "IC1") (pin "6") (pinfunction "PA3(PCINT27)_6") (pintype "bidirectional"))
    )
    (net (code "72") (name "unconnected-(IC1-PB6(CLKI,PCINT6)-Pad7)") (class "Default")
      (node (ref "IC1") (pin "7") (pinfunction "PB6(CLKI,PCINT6)_7") (pintype "bidirectional"))
    )
    (net (code "73") (name "unconnected-(IC1-PC7(PCINT15)-Pad20)") (class "Default")
      (node (ref "IC1") (pin "20") (pinfunction "PC7(PCINT15)_20") (pintype "bidirectional"))
    )
    (net (code "74") (name "unconnected-(IC2.1-OS-Pad3)") (class "Default")
      (node (ref "IC2.1") (pin "3") (pinfunction "OS_3") (pintype "output"))
    )
    (net (code "75") (name "unconnected-(IC3.1-MOT0-Pad9)") (class "Default")
      (node (ref "IC3.1") (pin "9") (pinfunction "MOT0_9") (pintype "bidirectional"))
    )
    (net (code "76") (name "unconnected-(IC3.1-SM-Pad12)") (class "Default")
      (node (ref "IC3.1") (pin "12") (pinfunction "SM_12") (pintype "bidirectional"))
    )
    (net (code "77") (name "unconnected-(IC3.1-TOG-Pad7)") (class "Default")
      (node (ref "IC3.1") (pin "7") (pinfunction "TOG_7") (pintype "bidirectional"))
    )
    (net (code "78") (name "unconnected-(IC6.1-K1-Pad19)") (class "Default")
      (node (ref "IC6.1") (pin "19") (pinfunction "K1_19") (pintype "bidirectional"))
    )
    (net (code "79") (name "unconnected-(IC6.1-K2-Pad20)") (class "Default")
      (node (ref "IC6.1") (pin "20") (pinfunction "K2_20") (pintype "bidirectional"))
    )
    (net (code "80") (name "unconnected-(SW1.1-A1-Pad2)") (class "Default")
      (node (ref "SW1.1") (pin "2") (pinfunction "A1_2") (pintype "bidirectional"))
    )
    (net (code "81") (name "unconnected-(SW1.1-B1-Pad4)") (class "Default")
      (node (ref "SW1.1") (pin "4") (pinfunction "B1_4") (pintype "bidirectional"))
    )
    (net (code "82") (name "unconnected-(X2.1-D+-Pad3)") (class "Default")
      (node (ref "X2.1") (pin "3") (pinfunction "D+_3") (pintype "bidirectional"))
    )
    (net (code "83") (name "unconnected-(X2.1-D--Pad2)") (class "Default")
      (node (ref "X2.1") (pin "2") (pinfunction "D-_2") (pintype "bidirectional"))
    )
    (net (code "84") (name "unconnected-(X2.1-ID-Pad4)") (class "Default")
      (node (ref "X2.1") (pin "4") (pinfunction "ID_4") (pintype "bidirectional"))
    )
  )
)
